# DROP.net
KiCad netlist of a schematic drawn in Altium Designer
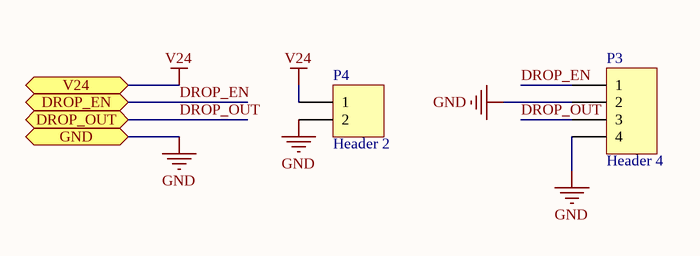
[diagram p0: DROP.SchDoc]

(export (version "E")
  (design (tool "Eeschema 10.0.6"))
  (components
    (comp (ref "P3")
      (value "Header 4")
      (footprint "4P_XH2.54")
      (description "Header, 4-Pin")
      (fields (field (name "PUBLISHER") "Altium Limited"))
      (libsource (lib "Miscellaneous Connectors") (part "Header 4"))
    )
    (comp (ref "P4")
      (value "Header 2")
      (footprint "2P_XH2.54")
      (description "Header, 2-Pin")
      (fields (field (name "PUBLISHER") "Altium Limited"))
      (libsource (lib "Miscellaneous Connectors") (part "Header 2"))
    )
  )
  (nets
    (net (code "1") (name "/DROP_EN") (class "Default")
      (node (ref "P3") (pin "1") (pinfunction "1_1") (pintype "passive"))
    )
    (net (code "2") (name "/DROP_OUT") (class "Default")
      (node (ref "P3") (pin "3") (pinfunction "3_3") (pintype "passive"))
    )
    (net (code "3") (name "GND") (class "Default")
      (node (ref "P3") (pin "2") (pinfunction "2_2") (pintype "passive"))
      (node (ref "P3") (pin "4") (pinfunction "4_4") (pintype "passive"))
      (node (ref "P4") (pin "2") (pinfunction "2_2") (pintype "passive"))
    )
    (net (code "4") (name "V24") (class "Default")
      (node (ref "P4") (pin "1") (pinfunction "1_1") (pintype "passive"))
    )
  )
)
